# oshi-fuse-board-mk-3_5x20mm.net
KiCad netlist of a schematic drawn in EAGLE
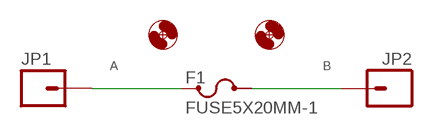
[diagram p0: schematic, sheet 1]

(export (version "E")
  (design (tool "Eeschema 10.0.6"))
  (components
    (comp (ref "F1")
      (value "FUSE5X20MM-1")
      (footprint "eagle-import:FUSE_5MM")
      (libsource (lib "eagle-import") (part "FUSE5X20MM-1"))
    )
    (comp (ref "H1")
      (value "HOLE#2")
      (footprint "eagle-import:HOLE-#2")
      (libsource (lib "eagle-import") (part "HOLE#2"))
    )
    (comp (ref "H2")
      (value "HOLE#2")
      (footprint "eagle-import:HOLE-#2")
      (libsource (lib "eagle-import") (part "HOLE#2"))
    )
    (comp (ref "JP1")
      (value "M01SCREWITGOOD")
      (footprint "eagle-import:1X01-RING-TERM-6-32-FAT")
      (libsource (lib "eagle-import") (part "M01SCREWITGOOD"))
    )
    (comp (ref "JP2")
      (value "M01SCREWITGOOD")
      (footprint "eagle-import:1X01-RING-TERM-6-32-FAT")
      (libsource (lib "eagle-import") (part "M01SCREWITGOOD"))
    )
  )
  (nets
    (net (code "1") (name "/A") (class "Default")
      (node (ref "F1") (pin "1") (pinfunction "1_1") (pintype "passive"))
      (node (ref "F1") (pin "2") (pinfunction "1_2") (pintype "passive"))
      (node (ref "JP1") (pin "P$1") (pinfunction "1_P$1") (pintype "passive"))
      (node (ref "JP1") (pin "P$2") (pinfunction "1_P$2") (pintype "passive"))
      (node (ref "JP1") (pin "P$3") (pinfunction "1_P$3") (pintype "passive"))
      (node (ref "JP1") (pin "P$4") (pinfunction "1_P$4") (pintype "passive"))
    )
    (net (code "2") (name "/B") (class "Default")
      (node (ref "F1") (pin "3") (pinfunction "2_3") (pintype "passive"))
      (node (ref "F1") (pin "4") (pinfunction "2_4") (pintype "passive"))
      (node (ref "JP2") (pin "P$1") (pinfunction "1_P$1") (pintype "passive"))
      (node (ref "JP2") (pin "P$2") (pinfunction "1_P$2") (pintype "passive"))
      (node (ref "JP2") (pin "P$3") (pinfunction "1_P$3") (pintype "passive"))
      (node (ref "JP2") (pin "P$4") (pinfunction "1_P$4") (pintype "passive"))
    )
  )
)
